# 01_Power.net
KiCad netlist of a schematic drawn in Altium Designer
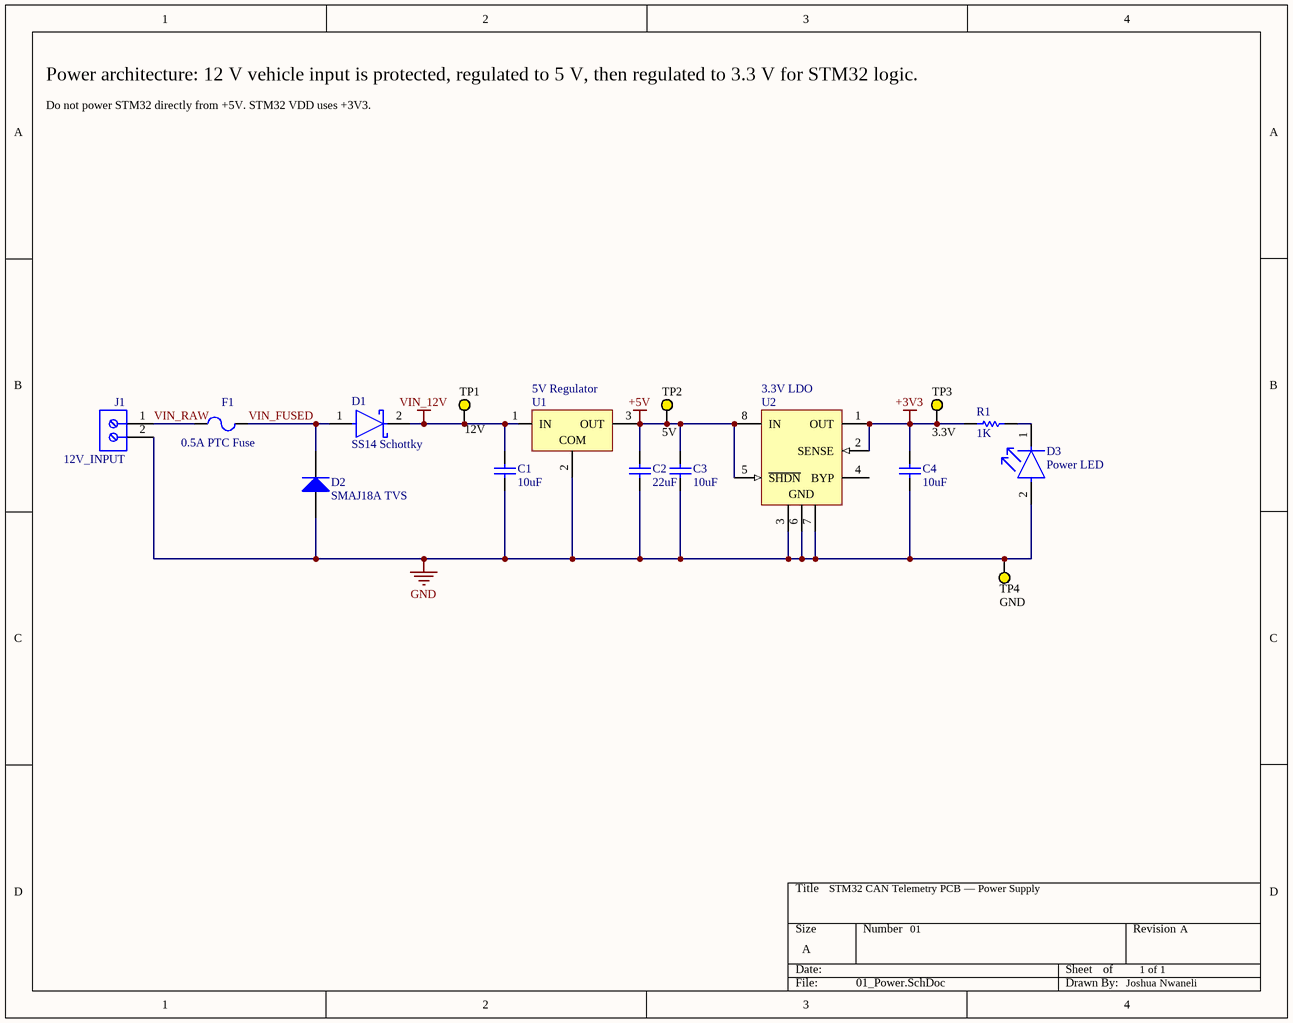
[diagram p0: 01_Power.SchDoc]

(export (version "E")
  (design (tool "Eeschema 10.0.6"))
  (components
    (comp (ref "C1")
      (value "10uF")
      (footprint "CAPC2013X140X50ML20T25")
      (fields
        (field (name "MANUFACTURER") "AVX Interconnect / Elco")
        (field (name "PART NUMBER") "0805ZC106KAT2A")
      )
      (libsource (lib "Altium Content Vault") (part "CAP"))
    )
    (comp (ref "C2")
      (value "22uF")
      (footprint "CAPC1206(3216)190_N")
      (description "CAP 22uF 10V ±20% 1206 (3216 Metric) Thickness 1.9mm SMD")
      (fields (field (name "TOLERANCE") "Â±20%"))
      (libsource (lib "Altium Content Vault") (part "CAP"))
    )
    (comp (ref "C3")
      (value "10uF")
      (footprint "CAPC2013X140X50ML20T25")
      (fields
        (field (name "MANUFACTURER") "AVX Interconnect / Elco")
        (field (name "PART NUMBER") "0805ZC106KAT2A")
      )
      (libsource (lib "Altium Content Vault") (part "CAP"))
    )
    (comp (ref "C4")
      (value "10uF")
      (footprint "CAPC2013X140X50ML20T25")
      (fields
        (field (name "MANUFACTURER") "AVX Interconnect / Elco")
        (field (name "PART NUMBER") "0805ZC106KAT2A")
      )
      (libsource (lib "Altium Content Vault") (part "CAP"))
    )
    (comp (ref "D1")
      (value "SS14 Schottky")
      (footprint "FP-403AE-MFG")
      (description "DIODE SCHOTTKY 40V 1A SMA")
      (fields
        (field (name "MANUFACTURER PART NUMBER") "SS14")
        (field (name "MANUFACTURER") "ON Semiconductor")
      )
      (libsource (lib "Altium Content Vault") (part "360ad2f4ac25a952324d13796385471"))
    )
    (comp (ref "D2")
      (value "SMAJ18A TVS")
      (footprint "VISH-DO-214AC-2_M")
      (fields
        (field (name "MANUFACTURER") "Vishay Semiconductor")
        (field (name "PARTNUMBER") "SMAJ18A-E3/61")
      )
      (libsource (lib "Altium Content Vault") (part "VISH-K1A2-2"))
    )
    (comp (ref "D3")
      (value "Power LED")
      (footprint "FP-SML-LXT0805IW-TR-MFG")
      (description "LED RED DIFFUSED SMD")
      (libsource (lib "Altium Content Vault") (part "8706943c75ba83719d021d2fdc84c58"))
    )
    (comp (ref "F1")
      (value "0.5A PTC Fuse")
      (footprint "LFUS-1812L05030PR_V")
      (description "PTC Resettable Fuse, 0.8 W, 30 V, -40 to 85 degC, 2-Pin SMD, RoHS, Tape and Reel")
      (fields (field (name "MANUFACTURER") "Littelfuse-Inc."))
      (libsource (lib "Altium Content Vault") (part "FUSE-2"))
    )
    (comp (ref "J1")
      (value "12V_INPUT")
      (footprint "691249510002")
      (description "Terminal Block, 5.08MM Pitch, Double Level Horizontal, 12-30 AWG, 2 Pin")
      (libsource (lib "Altium Content Vault") (part "TBL - 1R - 02P - Screw"))
    )
    (comp (ref "R1")
      (value "1K")
      (footprint "RESC2013X50X30ML20T20")
      (fields (field (name "MANUFACTURER") "Vishay Dale") (field (name "PART NUMBER") "CRCW08051K00FKTC"))
      (libsource (lib "Altium Content Vault") (part "RES"))
    )
    (comp (ref "TP1")
      (value "12V")
      (footprint "KSTN-5014_V")
      (description "12V Test Point")
      (fields (field (name "MANUFACTURER") "Keystone"))
      (libsource (lib "Altium Content Vault") (part "TESTPOINT_YELLOW"))
    )
    (comp (ref "TP2")
      (value "5V")
      (footprint "KSTN-5014_V")
      (description "5V Test Point")
      (fields (field (name "MANUFACTURER") "Keystone"))
      (libsource (lib "Altium Content Vault") (part "TESTPOINT_YELLOW"))
    )
    (comp (ref "TP3")
      (value "3.3V")
      (footprint "KSTN-5014_V")
      (description "3.3V Test Point")
      (fields (field (name "MANUFACTURER") "Keystone"))
      (libsource (lib "Altium Content Vault") (part "TESTPOINT_YELLOW"))
    )
    (comp (ref "TP4")
      (value "GND")
      (footprint "KSTN-5014_V")
      (description "Ground Test Point")
      (fields (field (name "MANUFACTURER") "Keystone"))
      (libsource (lib "Altium Content Vault") (part "TESTPOINT_YELLOW"))
    )
    (comp (ref "U1")
      (value "5V Regulator")
      (footprint "LP3")
      (description "Regulates protected 12V input down to 5V")
      (fields (field (name "PARTNUMBER") "UA78M05IKCSE3") (field (name "MANUFACTURER") "Texas Instruments"))
      (libsource (lib "Altium Content Vault") (part "TI-UA78M05KCS3"))
    )
    (comp (ref "U2")
      (value "3.3V LDO")
      (footprint "LT-S8-8_N")
      (fields
        (field (name "MANUFACTURER") "Linear Technology")
        (field (name "PARTNUMBER") "LT1763IS8-3.3#PBF")
      )
      (libsource (lib "Altium Content Vault") (part "LT-LT1763-S8-8"))
    )
  )
  (nets
    (net (code "1") (name "+3V3") (class "Default")
      (node (ref "C4") (pin "2") (pinfunction "2_2") (pintype "passive"))
      (node (ref "R1") (pin "1") (pinfunction "1_1") (pintype "passive"))
      (node (ref "TP3") (pin "1") (pinfunction "1_1") (pintype "passive"))
      (node (ref "U2") (pin "1") (pinfunction "OUT_1") (pintype "power_in"))
      (node (ref "U2") (pin "2") (pinfunction "SENSE_2") (pintype "input"))
    )
    (net (code "2") (name "+5V") (class "Default")
      (node (ref "C2") (pin "1") (pinfunction "1_1") (pintype "passive"))
      (node (ref "C3") (pin "2") (pinfunction "2_2") (pintype "passive"))
      (node (ref "TP2") (pin "1") (pinfunction "1_1") (pintype "passive"))
      (node (ref "U1") (pin "3") (pinfunction "OUT_3") (pintype "power_in"))
      (node (ref "U2") (pin "5") (pinfunction "~{SHDN}_5") (pintype "input"))
      (node (ref "U2") (pin "8") (pinfunction "IN_8") (pintype "power_in"))
    )
    (net (code "3") (name "/VIN_FUSED") (class "Default")
      (node (ref "D1") (pin "1") (pinfunction "A_1") (pintype "passive"))
      (node (ref "D2") (pin "1") (pinfunction "K_1") (pintype "passive"))
      (node (ref "F1") (pin "2") (pinfunction "2_2") (pintype "passive"))
    )
    (net (code "4") (name "/VIN_RAW") (class "Default")
      (node (ref "F1") (pin "1") (pinfunction "1_1") (pintype "passive"))
      (node (ref "J1") (pin "1") (pinfunction "1_1") (pintype "passive"))
    )
    (net (code "5") (name "GND") (class "Default")
      (node (ref "C1") (pin "1") (pinfunction "1_1") (pintype "passive"))
      (node (ref "C2") (pin "2") (pinfunction "2_2") (pintype "passive"))
      (node (ref "C3") (pin "1") (pinfunction "1_1") (pintype "passive"))
      (node (ref "C4") (pin "1") (pinfunction "1_1") (pintype "passive"))
      (node (ref "D2") (pin "2") (pinfunction "A_2") (pintype "passive"))
      (node (ref "D3") (pin "2") (pinfunction "A_2") (pintype "passive"))
      (node (ref "J1") (pin "2") (pinfunction "2_2") (pintype "passive"))
      (node (ref "TP4") (pin "1") (pinfunction "1_1") (pintype "passive"))
      (node (ref "U1") (pin "2") (pinfunction "COM_2") (pintype "power_in"))
      (node (ref "U2") (pin "3") (pinfunction "GND_3") (pintype "power_in"))
      (node (ref "U2") (pin "6") (pinfunction "GND_6") (pintype "power_in"))
      (node (ref "U2") (pin "7") (pinfunction "GND_7") (pintype "power_in"))
    )
    (net (code "6") (name "Net-(D3-C)") (class "Default")
      (node (ref "D3") (pin "1") (pinfunction "C_1") (pintype "passive"))
      (node (ref "R1") (pin "2") (pinfunction "2_2") (pintype "passive"))
    )
    (net (code "7") (name "VIN_12V") (class "Default")
      (node (ref "C1") (pin "2") (pinfunction "2_2") (pintype "passive"))
      (node (ref "D1") (pin "2") (pinfunction "C_2") (pintype "passive"))
      (node (ref "TP1") (pin "1") (pinfunction "1_1") (pintype "passive"))
      (node (ref "U1") (pin "1") (pinfunction "IN_1") (pintype "power_in"))
    )
    (net (code "8") (name "unconnected-(U2-BYP-Pad4)") (class "Default")
      (node (ref "U2") (pin "4") (pinfunction "BYP_4") (pintype "passive"))
    )
  )
)
